# MPPT.net
KiCad netlist of a schematic drawn in EAGLE
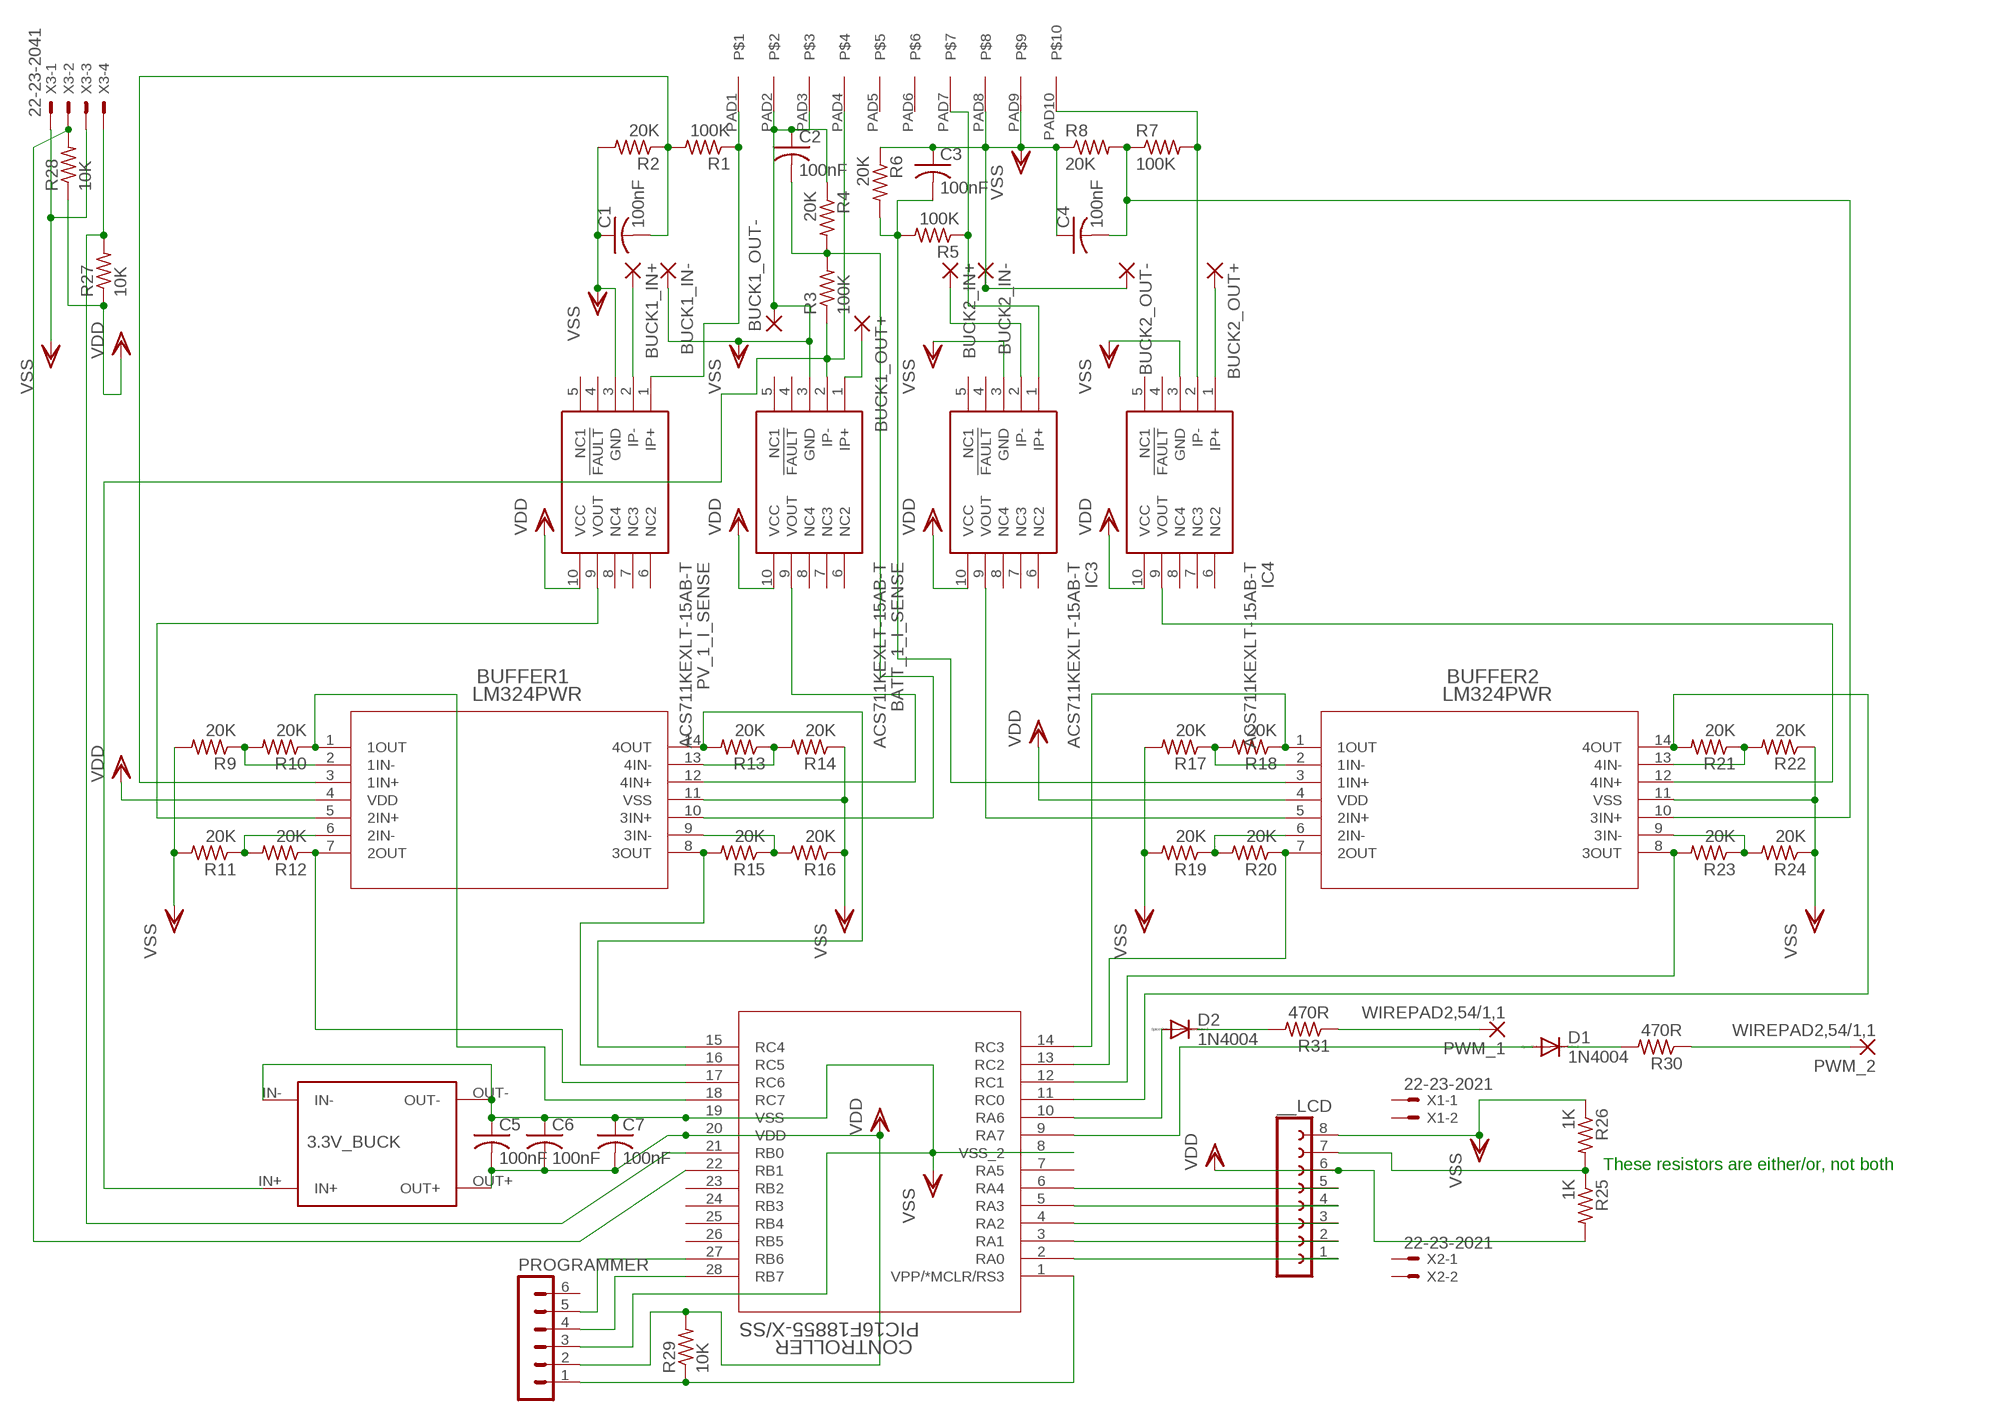
[diagram p0: schematic, sheet 1]

(export (version "E")
  (design (tool "Eeschema 10.0.6"))
  (components
    (comp (ref "3.3V_BUCK")
      (value "TINY_BUCK")
      (footprint "eagle-import:TINY_BUCK")
      (libsource (lib "eagle-import") (part "TINY_BUCK"))
    )
    (comp (ref "BATT_1_I_SENSE")
      (value "ACS711KEXLT-15AB-T")
      (footprint "eagle-import:EX-PACKAGE")
      (libsource (lib "eagle-import") (part "ACS711KEXLT-15AB-T"))
    )
    (comp (ref "BUCK1_IN+")
      (value "3,81/1,4")
      (footprint "eagle-import:3,81_1,4")
      (libsource (lib "eagle-import") (part "3,81/1,4"))
    )
    (comp (ref "BUCK1_IN-")
      (value "3,81/1,4")
      (footprint "eagle-import:3,81_1,4")
      (libsource (lib "eagle-import") (part "3,81/1,4"))
    )
    (comp (ref "BUCK1_OUT+")
      (value "3,81/1,4")
      (footprint "eagle-import:3,81_1,4")
      (libsource (lib "eagle-import") (part "3,81/1,4"))
    )
    (comp (ref "BUCK1_OUT-")
      (value "3,81/1,4")
      (footprint "eagle-import:3,81_1,4")
      (libsource (lib "eagle-import") (part "3,81/1,4"))
    )
    (comp (ref "BUCK2_IN+")
      (value "3,81/1,4")
      (footprint "eagle-import:3,81_1,4")
      (libsource (lib "eagle-import") (part "3,81/1,4"))
    )
    (comp (ref "BUCK2_IN-")
      (value "3,81/1,4")
      (footprint "eagle-import:3,81_1,4")
      (libsource (lib "eagle-import") (part "3,81/1,4"))
    )
    (comp (ref "BUCK2_OUT+")
      (value "3,81/1,4")
      (footprint "eagle-import:3,81_1,4")
      (libsource (lib "eagle-import") (part "3,81/1,4"))
    )
    (comp (ref "BUCK2_OUT-")
      (value "3,81/1,4")
      (footprint "eagle-import:3,81_1,4")
      (libsource (lib "eagle-import") (part "3,81/1,4"))
    )
    (comp (ref "BUFFER1")
      (value "LM324PWR")
      (footprint "eagle-import:PW14")
      (libsource (lib "eagle-import") (part "LM324PWR"))
    )
    (comp (ref "BUFFER2")
      (value "LM324PWR")
      (footprint "eagle-import:PW14")
      (libsource (lib "eagle-import") (part "LM324PWR"))
    )
    (comp (ref "C1")
      (value "100nF")
      (footprint "eagle-import:C0603")
      (libsource (lib "eagle-import") (part "C-USC0603"))
    )
    (comp (ref "C2")
      (value "100nF")
      (footprint "eagle-import:C0603")
      (libsource (lib "eagle-import") (part "C-USC0603"))
    )
    (comp (ref "C3")
      (value "100nF")
      (footprint "eagle-import:C0603")
      (libsource (lib "eagle-import") (part "C-USC0603"))
    )
    (comp (ref "C4")
      (value "100nF")
      (footprint "eagle-import:C0603")
      (libsource (lib "eagle-import") (part "C-USC0603"))
    )
    (comp (ref "C5")
      (value "100nF")
      (footprint "eagle-import:C0603")
      (libsource (lib "eagle-import") (part "C-USC0603"))
    )
    (comp (ref "C6")
      (value "100nF")
      (footprint "eagle-import:C0603")
      (libsource (lib "eagle-import") (part "C-USC0603"))
    )
    (comp (ref "C7")
      (value "100nF")
      (footprint "eagle-import:C0603")
      (libsource (lib "eagle-import") (part "C-USC0603"))
    )
    (comp (ref "CONTROLLER")
      (value "PIC16F18855-X/SS")
      (footprint "eagle-import:SSOP28_MC")
      (fields
        (field (name "MANUFACTURER_PART_NUMBER") "pic16f18855-x/ss")
        (field (name "COPYRIGHT") "Copyright (C) 2016 Accelerated Designs. All rights reserved")
      )
      (libsource (lib "eagle-import") (part "PIC16F18855-X/SS"))
    )
    (comp (ref "D1")
      (value "1N4004")
      (footprint "eagle-import:DO41-10")
      (libsource (lib "eagle-import") (part "1N4004"))
    )
    (comp (ref "D2")
      (value "1N4004")
      (footprint "eagle-import:DO41-10")
      (libsource (lib "eagle-import") (part "1N4004"))
    )
    (comp (ref "IC3")
      (value "ACS711KEXLT-15AB-T")
      (footprint "eagle-import:EX-PACKAGE")
      (libsource (lib "eagle-import") (part "ACS711KEXLT-15AB-T"))
    )
    (comp (ref "IC4")
      (value "ACS711KEXLT-15AB-T")
      (footprint "eagle-import:EX-PACKAGE")
      (libsource (lib "eagle-import") (part "ACS711KEXLT-15AB-T"))
    )
    (comp (ref "PROGRAMMER")
      (value "MA06-1")
      (footprint "eagle-import:MA06-1")
      (libsource (lib "eagle-import") (part "MA06-1"))
    )
    (comp (ref "PV_1_I_SENSE")
      (value "ACS711KEXLT-15AB-T")
      (footprint "eagle-import:EX-PACKAGE")
      (libsource (lib "eagle-import") (part "ACS711KEXLT-15AB-T"))
    )
    (comp (ref "PWM_1")
      (value "WIREPAD2,54/1,1")
      (footprint "eagle-import:2,54_1,1")
      (libsource (lib "eagle-import") (part "WIREPAD2,54/1,1"))
    )
    (comp (ref "PWM_2")
      (value "WIREPAD2,54/1,1")
      (footprint "eagle-import:2,54_1,1")
      (libsource (lib "eagle-import") (part "WIREPAD2,54/1,1"))
    )
    (comp (ref "R1")
      (value "100K")
      (footprint "eagle-import:R0603")
      (libsource (lib "eagle-import") (part "resistor_R-US_R0603"))
    )
    (comp (ref "R2")
      (value "20K")
      (footprint "eagle-import:R0603")
      (libsource (lib "eagle-import") (part "resistor_R-US_R0603"))
    )
    (comp (ref "R3")
      (value "100K")
      (footprint "eagle-import:R0603")
      (libsource (lib "eagle-import") (part "resistor_R-US_R0603"))
    )
    (comp (ref "R4")
      (value "20K")
      (footprint "eagle-import:R0603")
      (libsource (lib "eagle-import") (part "resistor_R-US_R0603"))
    )
    (comp (ref "R5")
      (value "100K")
      (footprint "eagle-import:R0603")
      (libsource (lib "eagle-import") (part "resistor_R-US_R0603"))
    )
    (comp (ref "R6")
      (value "20K")
      (footprint "eagle-import:R0603")
      (libsource (lib "eagle-import") (part "resistor_R-US_R0603"))
    )
    (comp (ref "R7")
      (value "100K")
      (footprint "eagle-import:R0603")
      (libsource (lib "eagle-import") (part "resistor_R-US_R0603"))
    )
    (comp (ref "R8")
      (value "20K")
      (footprint "eagle-import:R0603")
      (libsource (lib "eagle-import") (part "resistor_R-US_R0603"))
    )
    (comp (ref "R9")
      (value "20K")
      (footprint "eagle-import:R0603")
      (libsource (lib "eagle-import") (part "resistor_R-US_R0603"))
    )
    (comp (ref "R10")
      (value "20K")
      (footprint "eagle-import:R0603")
      (libsource (lib "eagle-import") (part "resistor_R-US_R0603"))
    )
    (comp (ref "R11")
      (value "20K")
      (footprint "eagle-import:R0603")
      (libsource (lib "eagle-import") (part "resistor_R-US_R0603"))
    )
    (comp (ref "R12")
      (value "20K")
      (footprint "eagle-import:R0603")
      (libsource (lib "eagle-import") (part "resistor_R-US_R0603"))
    )
    (comp (ref "R13")
      (value "20K")
      (footprint "eagle-import:R0603")
      (libsource (lib "eagle-import") (part "resistor_R-US_R0603"))
    )
    (comp (ref "R14")
      (value "20K")
      (footprint "eagle-import:R0603")
      (libsource (lib "eagle-import") (part "resistor_R-US_R0603"))
    )
    (comp (ref "R15")
      (value "20K")
      (footprint "eagle-import:R0603")
      (libsource (lib "eagle-import") (part "resistor_R-US_R0603"))
    )
    (comp (ref "R16")
      (value "20K")
      (footprint "eagle-import:R0603")
      (libsource (lib "eagle-import") (part "resistor_R-US_R0603"))
    )
    (comp (ref "R17")
      (value "20K")
      (footprint "eagle-import:R0603")
      (libsource (lib "eagle-import") (part "resistor_R-US_R0603"))
    )
    (comp (ref "R18")
      (value "20K")
      (footprint "eagle-import:R0603")
      (libsource (lib "eagle-import") (part "resistor_R-US_R0603"))
    )
    (comp (ref "R19")
      (value "20K")
      (footprint "eagle-import:R0603")
      (libsource (lib "eagle-import") (part "resistor_R-US_R0603"))
    )
    (comp (ref "R20")
      (value "20K")
      (footprint "eagle-import:R0603")
      (libsource (lib "eagle-import") (part "resistor_R-US_R0603"))
    )
    (comp (ref "R21")
      (value "20K")
      (footprint "eagle-import:R0603")
      (libsource (lib "eagle-import") (part "resistor_R-US_R0603"))
    )
    (comp (ref "R22")
      (value "20K")
      (footprint "eagle-import:R0603")
      (libsource (lib "eagle-import") (part "resistor_R-US_R0603"))
    )
    (comp (ref "R23")
      (value "20K")
      (footprint "eagle-import:R0603")
      (libsource (lib "eagle-import") (part "resistor_R-US_R0603"))
    )
    (comp (ref "R24")
      (value "20K")
      (footprint "eagle-import:R0603")
      (libsource (lib "eagle-import") (part "resistor_R-US_R0603"))
    )
    (comp (ref "R25")
      (value "1K")
      (footprint "eagle-import:R0603")
      (libsource (lib "eagle-import") (part "resistor_R-US_R0603"))
    )
    (comp (ref "R26")
      (value "1K")
      (footprint "eagle-import:R0603")
      (libsource (lib "eagle-import") (part "resistor_R-US_R0603"))
    )
    (comp (ref "R27")
      (value "10K")
      (footprint "eagle-import:R1206")
      (libsource (lib "eagle-import") (part "R-US_R1206"))
    )
    (comp (ref "R28")
      (value "10K")
      (footprint "eagle-import:R0603")
      (libsource (lib "eagle-import") (part "resistor_R-US_R0603"))
    )
    (comp (ref "R29")
      (value "10K")
      (footprint "eagle-import:R0603")
      (libsource (lib "eagle-import") (part "resistor_R-US_R0603"))
    )
    (comp (ref "R30")
      (value "470R")
      (footprint "eagle-import:R0603")
      (libsource (lib "eagle-import") (part "resistor_R-US_R0603"))
    )
    (comp (ref "R31")
      (value "470R")
      (footprint "eagle-import:R1206")
      (libsource (lib "eagle-import") (part "resistor_R-US_R1206"))
    )
    (comp (ref "U$1")
      (value "CONN-KF2EDG-10(5.08)E-BAYPLUGGABLECONNECTORS")
      (footprint "eagle-import:CONN-KF2EDG-10(5.08)")
      (libsource (lib "eagle-import") (part "CONN-KF2EDG-10(5.08)E-BAYPLUGGABLECONNECTORS"))
    )
    (comp (ref "X1")
      (value "22-23-2021")
      (footprint "eagle-import:22-23-2021")
      (fields (field (name "MF") "MOLEX"))
      (libsource (lib "eagle-import") (part "22-23-2021"))
    )
    (comp (ref "X2")
      (value "22-23-2021")
      (footprint "eagle-import:22-23-2021")
      (fields (field (name "MF") "MOLEX"))
      (libsource (lib "eagle-import") (part "22-23-2021"))
    )
    (comp (ref "X3")
      (value "22-23-2041")
      (footprint "eagle-import:22-23-2041")
      (fields (field (name "MF") "MOLEX"))
      (libsource (lib "eagle-import") (part "22-23-2041"))
    )
    (comp (ref "__LCD")
      (value "FE08-1")
      (footprint "eagle-import:FE08")
      (libsource (lib "eagle-import") (part "FE08-1"))
    )
  )
  (nets
    (net (code "1") (name "Net-(BATT_1_I_SENSE-IP+)") (class "Default")
      (node (ref "BATT_1_I_SENSE") (pin "1") (pinfunction "IP+_1") (pintype "bidirectional"))
      (node (ref "BUCK1_OUT+") (pin "1") (pinfunction "P_1") (pintype "passive"))
    )
    (net (code "2") (name "Net-(BATT_1_I_SENSE-IP-)") (class "Default")
      (node (ref "3.3V_BUCK") (pin "IN+") (pinfunction "IN+_IN+") (pintype "power_in"))
      (node (ref "BATT_1_I_SENSE") (pin "2") (pinfunction "IP-_2") (pintype "bidirectional"))
      (node (ref "R3") (pin "1") (pinfunction "1_1") (pintype "passive"))
      (node (ref "U$1") (pin "PAD4") (pinfunction "P$4_PAD4") (pintype "bidirectional"))
    )
    (net (code "3") (name "Net-(BATT_1_I_SENSE-VOUT)") (class "Default")
      (node (ref "BATT_1_I_SENSE") (pin "9") (pinfunction "VOUT_9") (pintype "bidirectional"))
      (node (ref "BUFFER1") (pin "12") (pinfunction "4IN+_12") (pintype "input"))
    )
    (net (code "4") (name "Net-(BUCK1_IN+-P)") (class "Default")
      (node (ref "BUCK1_IN+") (pin "1") (pinfunction "P_1") (pintype "passive"))
      (node (ref "PV_1_I_SENSE") (pin "2") (pinfunction "IP-_2") (pintype "bidirectional"))
    )
    (net (code "5") (name "Net-(BUCK2_IN+-P)") (class "Default")
      (node (ref "BUCK2_IN+") (pin "1") (pinfunction "P_1") (pintype "passive"))
      (node (ref "IC3") (pin "2") (pinfunction "IP-_2") (pintype "bidirectional"))
    )
    (net (code "6") (name "Net-(BUCK2_OUT+-P)") (class "Default")
      (node (ref "BUCK2_OUT+") (pin "1") (pinfunction "P_1") (pintype "passive"))
      (node (ref "IC4") (pin "1") (pinfunction "IP+_1") (pintype "bidirectional"))
    )
    (net (code "7") (name "Net-(BUFFER1-1IN+)") (class "Default")
      (node (ref "BUFFER1") (pin "3") (pinfunction "1IN+_3") (pintype "input"))
      (node (ref "C1") (pin "2") (pinfunction "2_2") (pintype "passive"))
      (node (ref "R1") (pin "2") (pinfunction "2_2") (pintype "passive"))
      (node (ref "R2") (pin "1") (pinfunction "1_1") (pintype "passive"))
    )
    (net (code "8") (name "Net-(BUFFER1-1IN-)") (class "Default")
      (node (ref "BUFFER1") (pin "2") (pinfunction "1IN-_2") (pintype "input"))
      (node (ref "R10") (pin "2") (pinfunction "2_2") (pintype "passive"))
      (node (ref "R9") (pin "1") (pinfunction "1_1") (pintype "passive"))
    )
    (net (code "9") (name "Net-(BUFFER1-1OUT)") (class "Default")
      (node (ref "BUFFER1") (pin "1") (pinfunction "1OUT_1") (pintype "output"))
      (node (ref "CONTROLLER") (pin "18") (pinfunction "RC7_18") (pintype "bidirectional"))
      (node (ref "R10") (pin "1") (pinfunction "1_1") (pintype "passive"))
    )
    (net (code "10") (name "Net-(BUFFER1-2IN+)") (class "Default")
      (node (ref "BUFFER1") (pin "5") (pinfunction "2IN+_5") (pintype "input"))
      (node (ref "PV_1_I_SENSE") (pin "9") (pinfunction "VOUT_9") (pintype "bidirectional"))
    )
    (net (code "11") (name "Net-(BUFFER1-2IN-)") (class "Default")
      (node (ref "BUFFER1") (pin "6") (pinfunction "2IN-_6") (pintype "input"))
      (node (ref "R11") (pin "1") (pinfunction "1_1") (pintype "passive"))
      (node (ref "R12") (pin "2") (pinfunction "2_2") (pintype "passive"))
    )
    (net (code "12") (name "Net-(BUFFER1-2OUT)") (class "Default")
      (node (ref "BUFFER1") (pin "7") (pinfunction "2OUT_7") (pintype "output"))
      (node (ref "CONTROLLER") (pin "17") (pinfunction "RC6_17") (pintype "bidirectional"))
      (node (ref "R12") (pin "1") (pinfunction "1_1") (pintype "passive"))
    )
    (net (code "13") (name "Net-(BUFFER1-3IN+)") (class "Default")
      (node (ref "BUFFER1") (pin "10") (pinfunction "3IN+_10") (pintype "input"))
      (node (ref "C2") (pin "2") (pinfunction "2_2") (pintype "passive"))
      (node (ref "R3") (pin "2") (pinfunction "2_2") (pintype "passive"))
      (node (ref "R4") (pin "2") (pinfunction "2_2") (pintype "passive"))
    )
    (net (code "14") (name "Net-(BUFFER1-3IN-)") (class "Default")
      (node (ref "BUFFER1") (pin "9") (pinfunction "3IN-_9") (pintype "input"))
      (node (ref "R15") (pin "1") (pinfunction "1_1") (pintype "passive"))
      (node (ref "R16") (pin "2") (pinfunction "2_2") (pintype "passive"))
    )
    (net (code "15") (name "Net-(BUFFER1-3OUT)") (class "Default")
      (node (ref "BUFFER1") (pin "8") (pinfunction "3OUT_8") (pintype "output"))
      (node (ref "CONTROLLER") (pin "16") (pinfunction "RC5_16") (pintype "bidirectional"))
      (node (ref "R15") (pin "2") (pinfunction "2_2") (pintype "passive"))
    )
    (net (code "16") (name "Net-(BUFFER1-4IN-)") (class "Default")
      (node (ref "BUFFER1") (pin "13") (pinfunction "4IN-_13") (pintype "input"))
      (node (ref "R13") (pin "1") (pinfunction "1_1") (pintype "passive"))
      (node (ref "R14") (pin "2") (pinfunction "2_2") (pintype "passive"))
    )
    (net (code "17") (name "Net-(BUFFER1-4OUT)") (class "Default")
      (node (ref "BUFFER1") (pin "14") (pinfunction "4OUT_14") (pintype "output"))
      (node (ref "CONTROLLER") (pin "15") (pinfunction "RC4_15") (pintype "bidirectional"))
      (node (ref "R13") (pin "2") (pinfunction "2_2") (pintype "passive"))
    )
    (net (code "18") (name "Net-(BUFFER2-1IN+)") (class "Default")
      (node (ref "BUFFER2") (pin "3") (pinfunction "1IN+_3") (pintype "input"))
      (node (ref "C3") (pin "2") (pinfunction "2_2") (pintype "passive"))
      (node (ref "R5") (pin "2") (pinfunction "2_2") (pintype "passive"))
      (node (ref "R6") (pin "2") (pinfunction "2_2") (pintype "passive"))
    )
    (net (code "19") (name "Net-(BUFFER2-1IN-)") (class "Default")
      (node (ref "BUFFER2") (pin "2") (pinfunction "1IN-_2") (pintype "input"))
      (node (ref "R17") (pin "1") (pinfunction "1_1") (pintype "passive"))
      (node (ref "R18") (pin "2") (pinfunction "2_2") (pintype "passive"))
    )
    (net (code "20") (name "Net-(BUFFER2-1OUT)") (class "Default")
      (node (ref "BUFFER2") (pin "1") (pinfunction "1OUT_1") (pintype "output"))
      (node (ref "CONTROLLER") (pin "14") (pinfunction "RC3_14") (pintype "bidirectional"))
      (node (ref "R18") (pin "1") (pinfunction "1_1") (pintype "passive"))
    )
    (net (code "21") (name "Net-(BUFFER2-2IN+)") (class "Default")
      (node (ref "BUFFER2") (pin "5") (pinfunction "2IN+_5") (pintype "input"))
      (node (ref "IC3") (pin "9") (pinfunction "VOUT_9") (pintype "bidirectional"))
    )
    (net (code "22") (name "Net-(BUFFER2-2IN-)") (class "Default")
      (node (ref "BUFFER2") (pin "6") (pinfunction "2IN-_6") (pintype "input"))
      (node (ref "R19") (pin "1") (pinfunction "1_1") (pintype "passive"))
      (node (ref "R20") (pin "2") (pinfunction "2_2") (pintype "passive"))
    )
    (net (code "23") (name "Net-(BUFFER2-2OUT)") (class "Default")
      (node (ref "BUFFER2") (pin "7") (pinfunction "2OUT_7") (pintype "output"))
      (node (ref "CONTROLLER") (pin "13") (pinfunction "RC2_13") (pintype "bidirectional"))
      (node (ref "R20") (pin "1") (pinfunction "1_1") (pintype "passive"))
    )
    (net (code "24") (name "Net-(BUFFER2-3IN+)") (class "Default")
      (node (ref "BUFFER2") (pin "10") (pinfunction "3IN+_10") (pintype "input"))
      (node (ref "C4") (pin "2") (pinfunction "2_2") (pintype "passive"))
      (node (ref "R7") (pin "1") (pinfunction "1_1") (pintype "passive"))
      (node (ref "R8") (pin "2") (pinfunction "2_2") (pintype "passive"))
    )
    (net (code "25") (name "Net-(BUFFER2-3IN-)") (class "Default")
      (node (ref "BUFFER2") (pin "9") (pinfunction "3IN-_9") (pintype "input"))
      (node (ref "R23") (pin "1") (pinfunction "1_1") (pintype "passive"))
      (node (ref "R24") (pin "2") (pinfunction "2_2") (pintype "passive"))
    )
    (net (code "26") (name "Net-(BUFFER2-3OUT)") (class "Default")
      (node (ref "BUFFER2") (pin "8") (pinfunction "3OUT_8") (pintype "output"))
      (node (ref "CONTROLLER") (pin "12") (pinfunction "RC1_12") (pintype "bidirectional"))
      (node (ref "R23") (pin "2") (pinfunction "2_2") (pintype "passive"))
    )
    (net (code "27") (name "Net-(BUFFER2-4IN+)") (class "Default")
      (node (ref "BUFFER2") (pin "12") (pinfunction "4IN+_12") (pintype "input"))
      (node (ref "IC4") (pin "9") (pinfunction "VOUT_9") (pintype "bidirectional"))
    )
    (net (code "28") (name "Net-(BUFFER2-4IN-)") (class "Default")
      (node (ref "BUFFER2") (pin "13") (pinfunction "4IN-_13") (pintype "input"))
      (node (ref "R21") (pin "1") (pinfunction "1_1") (pintype "passive"))
      (node (ref "R22") (pin "2") (pinfunction "2_2") (pintype "passive"))
    )
    (net (code "29") (name "Net-(BUFFER2-4OUT)") (class "Default")
      (node (ref "BUFFER2") (pin "14") (pinfunction "4OUT_14") (pintype "output"))
      (node (ref "CONTROLLER") (pin "11") (pinfunction "RC0_11") (pintype "bidirectional"))
      (node (ref "R21") (pin "2") (pinfunction "2_2") (pintype "passive"))
    )
    (net (code "30") (name "Net-(CONTROLLER-RA0)") (class "Default")
      (node (ref "CONTROLLER") (pin "2") (pinfunction "RA0_2") (pintype "bidirectional"))
      (node (ref "__LCD") (pin "1") (pinfunction "1_1") (pintype "passive"))
    )
    (net (code "31") (name "Net-(CONTROLLER-RA1)") (class "Default")
      (node (ref "CONTROLLER") (pin "3") (pinfunction "RA1_3") (pintype "bidirectional"))
      (node (ref "__LCD") (pin "2") (pinfunction "2_2") (pintype "passive"))
    )
    (net (code "32") (name "Net-(CONTROLLER-RA2)") (class "Default")
      (node (ref "CONTROLLER") (pin "4") (pinfunction "RA2_4") (pintype "bidirectional"))
      (node (ref "__LCD") (pin "3") (pinfunction "3_3") (pintype "passive"))
    )
    (net (code "33") (name "Net-(CONTROLLER-RA3)") (class "Default")
      (node (ref "CONTROLLER") (pin "5") (pinfunction "RA3_5") (pintype "bidirectional"))
      (node (ref "__LCD") (pin "4") (pinfunction "4_4") (pintype "passive"))
    )
    (net (code "34") (name "Net-(CONTROLLER-RA4)") (class "Default")
      (node (ref "CONTROLLER") (pin "6") (pinfunction "RA4_6") (pintype "bidirectional"))
      (node (ref "__LCD") (pin "5") (pinfunction "5_5") (pintype "passive"))
    )
    (net (code "35") (name "Net-(CONTROLLER-RA6)") (class "Default")
      (node (ref "CONTROLLER") (pin "10") (pinfunction "RA6_10") (pintype "bidirectional"))
      (node (ref "D2") (pin "A") (pinfunction "A_A") (pintype "passive"))
    )
    (net (code "36") (name "Net-(CONTROLLER-RA7)") (class "Default")
      (node (ref "CONTROLLER") (pin "9") (pinfunction "RA7_9") (pintype "bidirectional"))
      (node (ref "D1") (pin "A") (pinfunction "A_A") (pintype "passive"))
    )
    (net (code "37") (name "Net-(CONTROLLER-RB0)") (class "Default")
      (node (ref "CONTROLLER") (pin "21") (pinfunction "RB0_21") (pintype "bidirectional"))
      (node (ref "R27") (pin "2") (pinfunction "2_2") (pintype "passive"))
      (node (ref "X3") (pin "4") (pinfunction "S_4") (pintype "passive"))
    )
    (net (code "38") (name "Net-(CONTROLLER-RB1)") (class "Default")
      (node (ref "CONTROLLER") (pin "22") (pinfunction "RB1_22") (pintype "bidirectional"))
      (node (ref "R28") (pin "2") (pinfunction "2_2") (pintype "passive"))
      (node (ref "X3") (pin "2") (pinfunction "S_2") (pintype "passive"))
    )
    (net (code "39") (name "Net-(CONTROLLER-RB6)") (class "Default")
      (node (ref "CONTROLLER") (pin "27") (pinfunction "RB6_27") (pintype "bidirectional"))
      (node (ref "PROGRAMMER") (pin "5") (pinfunction "5_5") (pintype "passive"))
    )
    (net (code "40") (name "Net-(CONTROLLER-RB7)") (class "Default")
      (node (ref "CONTROLLER") (pin "28") (pinfunction "RB7_28") (pintype "bidirectional"))
      (node (ref "PROGRAMMER") (pin "4") (pinfunction "4_4") (pintype "passive"))
    )
    (net (code "41") (name "Net-(CONTROLLER-VPP{slash}*MCLR{slash}RS3)") (class "Default")
      (node (ref "CONTROLLER") (pin "1") (pinfunction "VPP/*MCLR/RS3_1") (pintype "bidirectional"))
      (node (ref "PROGRAMMER") (pin "1") (pinfunction "1_1") (pintype "passive"))
      (node (ref "R29") (pin "1") (pinfunction "1_1") (pintype "passive"))
    )
    (net (code "42") (name "Net-(D1-PadC)") (class "Default")
      (node (ref "D1") (pin "C") (pinfunction "C_C") (pintype "passive"))
      (node (ref "R30") (pin "2") (pinfunction "2_2") (pintype "passive"))
    )
    (net (code "43") (name "Net-(D2-PadC)") (class "Default")
      (node (ref "D2") (pin "C") (pinfunction "C_C") (pintype "passive"))
      (node (ref "R31") (pin "2") (pinfunction "2_2") (pintype "passive"))
    )
    (net (code "44") (name "Net-(IC3-IP+)") (class "Default")
      (node (ref "IC3") (pin "1") (pinfunction "IP+_1") (pintype "bidirectional"))
      (node (ref "R5") (pin "1") (pinfunction "1_1") (pintype "passive"))
      (node (ref "U$1") (pin "PAD7") (pinfunction "P$7_PAD7") (pintype "bidirectional"))
    )
    (net (code "45") (name "Net-(IC4-IP-)") (class "Default")
      (node (ref "IC4") (pin "2") (pinfunction "IP-_2") (pintype "bidirectional"))
      (node (ref "R7") (pin "2") (pinfunction "2_2") (pintype "passive"))
      (node (ref "U$1") (pin "PAD10") (pinfunction "P$10_PAD10") (pintype "bidirectional"))
    )
    (net (code "46") (name "Net-(PV_1_I_SENSE-IP+)") (class "Default")
      (node (ref "PV_1_I_SENSE") (pin "1") (pinfunction "IP+_1") (pintype "bidirectional"))
      (node (ref "R1") (pin "1") (pinfunction "1_1") (pintype "passive"))
      (node (ref "U$1") (pin "PAD1") (pinfunction "P$1_PAD1") (pintype "bidirectional"))
    )
    (net (code "47") (name "Net-(PWM_1-P)") (class "Default")
      (node (ref "PWM_1") (pin "1") (pinfunction "P_1") (pintype "passive"))
      (node (ref "R31") (pin "1") (pinfunction "1_1") (pintype "passive"))
    )
    (net (code "48") (name "Net-(PWM_2-P)") (class "Default")
      (node (ref "PWM_2") (pin "1") (pinfunction "P_1") (pintype "passive"))
      (node (ref "R30") (pin "1") (pinfunction "1_1") (pintype "passive"))
    )
    (net (code "49") (name "Net-(R25-Pad1)") (class "Default")
      (node (ref "R25") (pin "1") (pinfunction "1_1") (pintype "passive"))
      (node (ref "R26") (pin "2") (pinfunction "2_2") (pintype "passive"))
      (node (ref "__LCD") (pin "7") (pinfunction "7_7") (pintype "passive"))
    )
    (net (code "50") (name "VDD") (class "Default")
      (node (ref "3.3V_BUCK") (pin "OUT+") (pinfunction "OUT+_OUT+") (pintype "power_in"))
      (node (ref "BATT_1_I_SENSE") (pin "10") (pinfunction "VCC_10") (pintype "bidirectional"))
      (node (ref "BUFFER1") (pin "4") (pinfunction "VDD_4") (pintype "power_in"))
      (node (ref "BUFFER2") (pin "4") (pinfunction "VDD_4") (pintype "power_in"))
      (node (ref "C5") (pin "2") (pinfunction "2_2") (pintype "passive"))
      (node (ref "C6") (pin "2") (pinfunction "2_2") (pintype "passive"))
      (node (ref "C7") (pin "2") (pinfunction "2_2") (pintype "passive"))
      (node (ref "CONTROLLER") (pin "20") (pinfunction "VDD_20") (pintype "power_in"))
      (node (ref "IC3") (pin "10") (pinfunction "VCC_10") (pintype "bidirectional"))
      (node (ref "IC4") (pin "10") (pinfunction "VCC_10") (pintype "bidirectional"))
      (node (ref "PROGRAMMER") (pin "2") (pinfunction "2_2") (pintype "passive"))
      (node (ref "PV_1_I_SENSE") (pin "10") (pinfunction "VCC_10") (pintype "bidirectional"))
      (node (ref "R25") (pin "2") (pinfunction "2_2") (pintype "passive"))
      (node (ref "R27") (pin "1") (pinfunction "1_1") (pintype "passive"))
      (node (ref "R28") (pin "1") (pinfunction "1_1") (pintype "passive"))
      (node (ref "R29") (pin "2") (pinfunction "2_2") (pintype "passive"))
      (node (ref "__LCD") (pin "6") (pinfunction "6_6") (pintype "passive"))
    )
    (net (code "51") (name "VSS") (class "Default")
      (node (ref "3.3V_BUCK") (pin "IN-") (pinfunction "IN-_IN-") (pintype "power_in"))
      (node (ref "3.3V_BUCK") (pin "OUT-") (pinfunction "OUT-_OUT-") (pintype "power_in"))
      (node (ref "BATT_1_I_SENSE") (pin "3") (pinfunction "GND_3") (pintype "bidirectional"))
      (node (ref "BUCK1_IN-") (pin "1") (pinfunction "P_1") (pintype "passive"))
      (node (ref "BUCK1_OUT-") (pin "1") (pinfunction "P_1") (pintype "passive"))
      (node (ref "BUCK2_IN-") (pin "1") (pinfunction "P_1") (pintype "passive"))
      (node (ref "BUCK2_OUT-") (pin "1") (pinfunction "P_1") (pintype "passive"))
      (node (ref "BUFFER1") (pin "11") (pinfunction "VSS_11") (pintype "power_in"))
      (node (ref "BUFFER2") (pin "11") (pinfunction "VSS_11") (pintype "power_in"))
      (node (ref "C1") (pin "1") (pinfunction "1_1") (pintype "passive"))
      (node (ref "C2") (pin "1") (pinfunction "1_1") (pintype "passive"))
      (node (ref "C3") (pin "1") (pinfunction "1_1") (pintype "passive"))
      (node (ref "C4") (pin "1") (pinfunction "1_1") (pintype "passive"))
      (node (ref "C5") (pin "1") (pinfunction "1_1") (pintype "passive"))
      (node (ref "C6") (pin "1") (pinfunction "1_1") (pintype "passive"))
      (node (ref "C7") (pin "1") (pinfunction "1_1") (pintype "passive"))
      (node (ref "CONTROLLER") (pin "19") (pinfunction "VSS_19") (pintype "power_in"))
      (node (ref "CONTROLLER") (pin "8") (pinfunction "VSS_2_8") (pintype "power_in"))
      (node (ref "IC3") (pin "3") (pinfunction "GND_3") (pintype "bidirectional"))
      (node (ref "IC4") (pin "3") (pinfunction "GND_3") (pintype "bidirectional"))
      (node (ref "PROGRAMMER") (pin "3") (pinfunction "3_3") (pintype "passive"))
      (node (ref "PV_1_I_SENSE") (pin "3") (pinfunction "GND_3") (pintype "bidirectional"))
      (node (ref "R11") (pin "2") (pinfunction "2_2") (pintype "passive"))
      (node (ref "R14") (pin "1") (pinfunction "1_1") (pintype "passive"))
      (node (ref "R16") (pin "1") (pinfunction "1_1") (pintype "passive"))
      (node (ref "R17") (pin "2") (pinfunction "2_2") (pintype "passive"))
      (node (ref "R19") (pin "2") (pinfunction "2_2") (pintype "passive"))
      (node (ref "R2") (pin "2") (pinfunction "2_2") (pintype "passive"))
      (node (ref "R22") (pin "1") (pinfunction "1_1") (pintype "passive"))
      (node (ref "R24") (pin "1") (pinfunction "1_1") (pintype "passive"))
      (node (ref "R26") (pin "1") (pinfunction "1_1") (pintype "passive"))
      (node (ref "R4") (pin "1") (pinfunction "1_1") (pintype "passive"))
      (node (ref "R6") (pin "1") (pinfunction "1_1") (pintype "passive"))
      (node (ref "R8") (pin "1") (pinfunction "1_1") (pintype "passive"))
      (node (ref "R9") (pin "2") (pinfunction "2_2") (pintype "passive"))
      (node (ref "U$1") (pin "PAD2") (pinfunction "P$2_PAD2") (pintype "bidirectional"))
      (node (ref "U$1") (pin "PAD3") (pinfunction "P$3_PAD3") (pintype "bidirectional"))
      (node (ref "U$1") (pin "PAD8") (pinfunction "P$8_PAD8") (pintype "bidirectional"))
      (node (ref "U$1") (pin "PAD9") (pinfunction "P$9_PAD9") (pintype "bidirectional"))
      (node (ref "X3") (pin "1") (pinfunction "S_1") (pintype "passive"))
      (node (ref "X3") (pin "3") (pinfunction "S_3") (pintype "passive"))
      (node (ref "__LCD") (pin "8") (pinfunction "8_8") (pintype "passive"))
    )
    (net (code "52") (name "unconnected-(BATT_1_I_SENSE-NC1-Pad5)") (class "Default")
      (node (ref "BATT_1_I_SENSE") (pin "5") (pinfunction "NC1_5") (pintype "bidirectional"))
    )
    (net (code "53") (name "unconnected-(BATT_1_I_SENSE-NC2-Pad6)") (class "Default")
      (node (ref "BATT_1_I_SENSE") (pin "6") (pinfunction "NC2_6") (pintype "bidirectional"))
    )
    (net (code "54") (name "unconnected-(BATT_1_I_SENSE-NC3-Pad7)") (class "Default")
      (node (ref "BATT_1_I_SENSE") (pin "7") (pinfunction "NC3_7") (pintype "bidirectional"))
    )
    (net (code "55") (name "unconnected-(BATT_1_I_SENSE-NC4-Pad8)") (class "Default")
      (node (ref "BATT_1_I_SENSE") (pin "8") (pinfunction "NC4_8") (pintype "bidirectional"))
    )
    (net (code "56") (name "unconnected-(BATT_1_I_SENSE-~{FAULT}-Pad4)") (class "Default")
      (node (ref "BATT_1_I_SENSE") (pin "4") (pinfunction "~{FAULT}_4") (pintype "bidirectional"))
    )
    (net (code "57") (name "unconnected-(CONTROLLER-RA5-Pad7)") (class "Default")
      (node (ref "CONTROLLER") (pin "7") (pinfunction "RA5_7") (pintype "bidirectional"))
    )
    (net (code "58") (name "unconnected-(CONTROLLER-RB2-Pad23)") (class "Default")
      (node (ref "CONTROLLER") (pin "23") (pinfunction "RB2_23") (pintype "bidirectional"))
    )
    (net (code "59") (name "unconnected-(CONTROLLER-RB3-Pad24)") (class "Default")
      (node (ref "CONTROLLER") (pin "24") (pinfunction "RB3_24") (pintype "bidirectional"))
    )
    (net (code "60") (name "unconnected-(CONTROLLER-RB4-Pad25)") (class "Default")
      (node (ref "CONTROLLER") (pin "25") (pinfunction "RB4_25") (pintype "bidirectional"))
    )
    (net (code "61") (name "unconnected-(CONTROLLER-RB5-Pad26)") (class "Default")
      (node (ref "CONTROLLER") (pin "26") (pinfunction "RB5_26") (pintype "bidirectional"))
    )
    (net (code "62") (name "unconnected-(IC3-NC1-Pad5)") (class "Default")
      (node (ref "IC3") (pin "5") (pinfunction "NC1_5") (pintype "bidirectional"))
    )
    (net (code "63") (name "unconnected-(IC3-NC2-Pad6)") (class "Default")
      (node (ref "IC3") (pin "6") (pinfunction "NC2_6") (pintype "bidirectional"))
    )
    (net (code "64") (name "unconnected-(IC3-NC3-Pad7)") (class "Default")
      (node (ref "IC3") (pin "7") (pinfunction "NC3_7") (pintype "bidirectional"))
    )
    (net (code "65") (name "unconnected-(IC3-NC4-Pad8)") (class "Default")
      (node (ref "IC3") (pin "8") (pinfunction "NC4_8") (pintype "bidirectional"))
    )
    (net (code "66") (name "unconnected-(IC3-~{FAULT}-Pad4)") (class "Default")
      (node (ref "IC3") (pin "4") (pinfunction "~{FAULT}_4") (pintype "bidirectional"))
    )
    (net (code "67") (name "unconnected-(IC4-NC1-Pad5)") (class "Default")
      (node (ref "IC4") (pin "5") (pinfunction "NC1_5") (pintype "bidirectional"))
    )
    (net (code "68") (name "unconnected-(IC4-NC2-Pad6)") (class "Default")
      (node (ref "IC4") (pin "6") (pinfunction "NC2_6") (pintype "bidirectional"))
    )
    (net (code "69") (name "unconnected-(IC4-NC3-Pad7)") (class "Default")
      (node (ref "IC4") (pin "7") (pinfunction "NC3_7") (pintype "bidirectional"))
    )
    (net (code "70") (name "unconnected-(IC4-NC4-Pad8)") (class "Default")
      (node (ref "IC4") (pin "8") (pinfunction "NC4_8") (pintype "bidirectional"))
    )
    (net (code "71") (name "unconnected-(IC4-~{FAULT}-Pad4)") (class "Default")
      (node (ref "IC4") (pin "4") (pinfunction "~{FAULT}_4") (pintype "bidirectional"))
    )
    (net (code "72") (name "unconnected-(PROGRAMMER-Pad6)") (class "Default")
      (node (ref "PROGRAMMER") (pin "6") (pinfunction "6_6") (pintype "passive"))
    )
    (net (code "73") (name "unconnected-(PV_1_I_SENSE-NC1-Pad5)") (class "Default")
      (node (ref "PV_1_I_SENSE") (pin "5") (pinfunction "NC1_5") (pintype "bidirectional"))
    )
    (net (code "74") (name "unconnected-(PV_1_I_SENSE-NC2-Pad6)") (class "Default")
      (node (ref "PV_1_I_SENSE") (pin "6") (pinfunction "NC2_6") (pintype "bidirectional"))
    )
    (net (code "75") (name "unconnected-(PV_1_I_SENSE-NC3-Pad7)") (class "Default")
      (node (ref "PV_1_I_SENSE") (pin "7") (pinfunction "NC3_7") (pintype "bidirectional"))
    )
    (net (code "76") (name "unconnected-(PV_1_I_SENSE-NC4-Pad8)") (class "Default")
      (node (ref "PV_1_I_SENSE") (pin "8") (pinfunction "NC4_8") (pintype "bidirectional"))
    )
    (net (code "77") (name "unconnected-(PV_1_I_SENSE-~{FAULT}-Pad4)") (class "Default")
      (node (ref "PV_1_I_SENSE") (pin "4") (pinfunction "~{FAULT}_4") (pintype "bidirectional"))
    )
    (net (code "78") (name "unconnected-(U$1-P$5-PadPAD5)") (class "Default")
      (node (ref "U$1") (pin "PAD5") (pinfunction "P$5_PAD5") (pintype "bidirectional"))
    )
    (net (code "79") (name "unconnected-(U$1-P$6-PadPAD6)") (class "Default")
      (node (ref "U$1") (pin "PAD6") (pinfunction "P$6_PAD6") (pintype "bidirectional"))
    )
    (net (code "80") (name "unconnected-(X1A-S-Pad1)") (class "Default")
      (node (ref "X1") (pin "1") (pinfunction "S_1") (pintype "passive"))
    )
    (net (code "81") (name "unconnected-(X1B-S-Pad2)") (class "Default")
      (node (ref "X1") (pin "2") (pinfunction "S_2") (pintype "passive"))
    )
    (net (code "82") (name "unconnected-(X2A-S-Pad1)") (class "Default")
      (node (ref "X2") (pin "1") (pinfunction "S_1") (pintype "passive"))
    )
    (net (code "83") (name "unconnected-(X2B-S-Pad2)") (class "Default")
      (node (ref "X2") (pin "2") (pinfunction "S_2") (pintype "passive"))
    )
  )
)
